# Relay_Control.net
KiCad netlist of a schematic drawn in Altium Designer
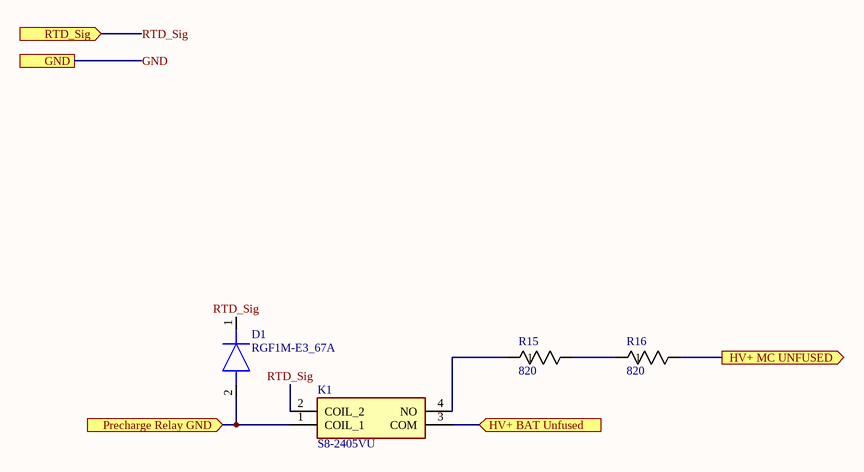
[diagram p0: Relay_Control.SchDoc]

(export (version "E")
  (design (tool "Eeschema 10.0.6"))
  (components
    (comp (ref "D1")
      (value "RGF1M-E3_67A")
      (footprint "DIOM5426X300N")
      (description "Diode")
      (fields
        (field (name "MANUFACTURER_PART_NUMBER") "RGF1M-E3/67A")
        (field (name "MOUSER PART NUMBER") "625-RGF1M-E3")
      )
      (libsource (lib "SamacSys") (part "RGF1M-E3_67A"))
    )
    (comp (ref "K1")
      (value "S8-2405VU")
      (footprint "SamacSys:S82405VU")
      (description "Relay or Contactor")
      (fields (field (name "MOUSER PART NUMBER") "285-S8-2405VU"))
      (libsource (lib "*") (part "S8-2405VU"))
    )
    (comp (ref "R15")
      (value "820")
      (footprint "RES_TWM10_OHM")
      (description "No Description Available")
      (fields
        (field (name "MANUFACTURER_PART_NUMBER") "TWW10J820E")
        (field (name "COPYRIGHT") "Copyright (C) 2025 Ultra Librarian. All rights reserved.")
      )
      (libsource (lib "SamacSys") (part "TWW10J820E"))
    )
    (comp (ref "R16")
      (value "820")
      (footprint "RES_TWM10_OHM")
      (description "No Description Available")
      (fields
        (field (name "MANUFACTURER_PART_NUMBER") "TWW10J820E")
        (field (name "COPYRIGHT") "Copyright (C) 2025 Ultra Librarian. All rights reserved.")
      )
      (libsource (lib "SamacSys") (part "TWW10J820E"))
    )
  )
  (nets
    (net (code "2") (name "/HV+ BAT Unfused") (class "Default")
      (node (ref "K1") (pin "3") (pinfunction "COM_3") (pintype "passive"))
    )
    (net (code "3") (name "/HV+ MC UNFUSED") (class "Default")
      (node (ref "R16") (pin "2") (pinfunction "2_2") (pintype "passive"))
    )
    (net (code "4") (name "/Precharge Relay GND") (class "Default")
      (node (ref "D1") (pin "2") (pinfunction "A_2") (pintype "passive"))
      (node (ref "K1") (pin "1") (pinfunction "COIL_1_1") (pintype "passive"))
    )
    (net (code "5") (name "/RTD_Sig") (class "Default")
      (node (ref "D1") (pin "1") (pinfunction "K_1") (pintype "passive"))
      (node (ref "K1") (pin "2") (pinfunction "COIL_2_2") (pintype "passive"))
    )
    (net (code "6") (name "Net-(K1-NO)") (class "Default")
      (node (ref "K1") (pin "4") (pinfunction "NO_4") (pintype "passive"))
      (node (ref "R15") (pin "1") (pinfunction "1_1") (pintype "passive"))
    )
    (net (code "7") (name "Net-(R15-Pad2)") (class "Default")
      (node (ref "R15") (pin "2") (pinfunction "2_2") (pintype "passive"))
      (node (ref "R16") (pin "1") (pinfunction "1_1") (pintype "passive"))
    )
  )
)
